# Control_Moway.net
KiCad netlist of a schematic drawn in Altium Designer
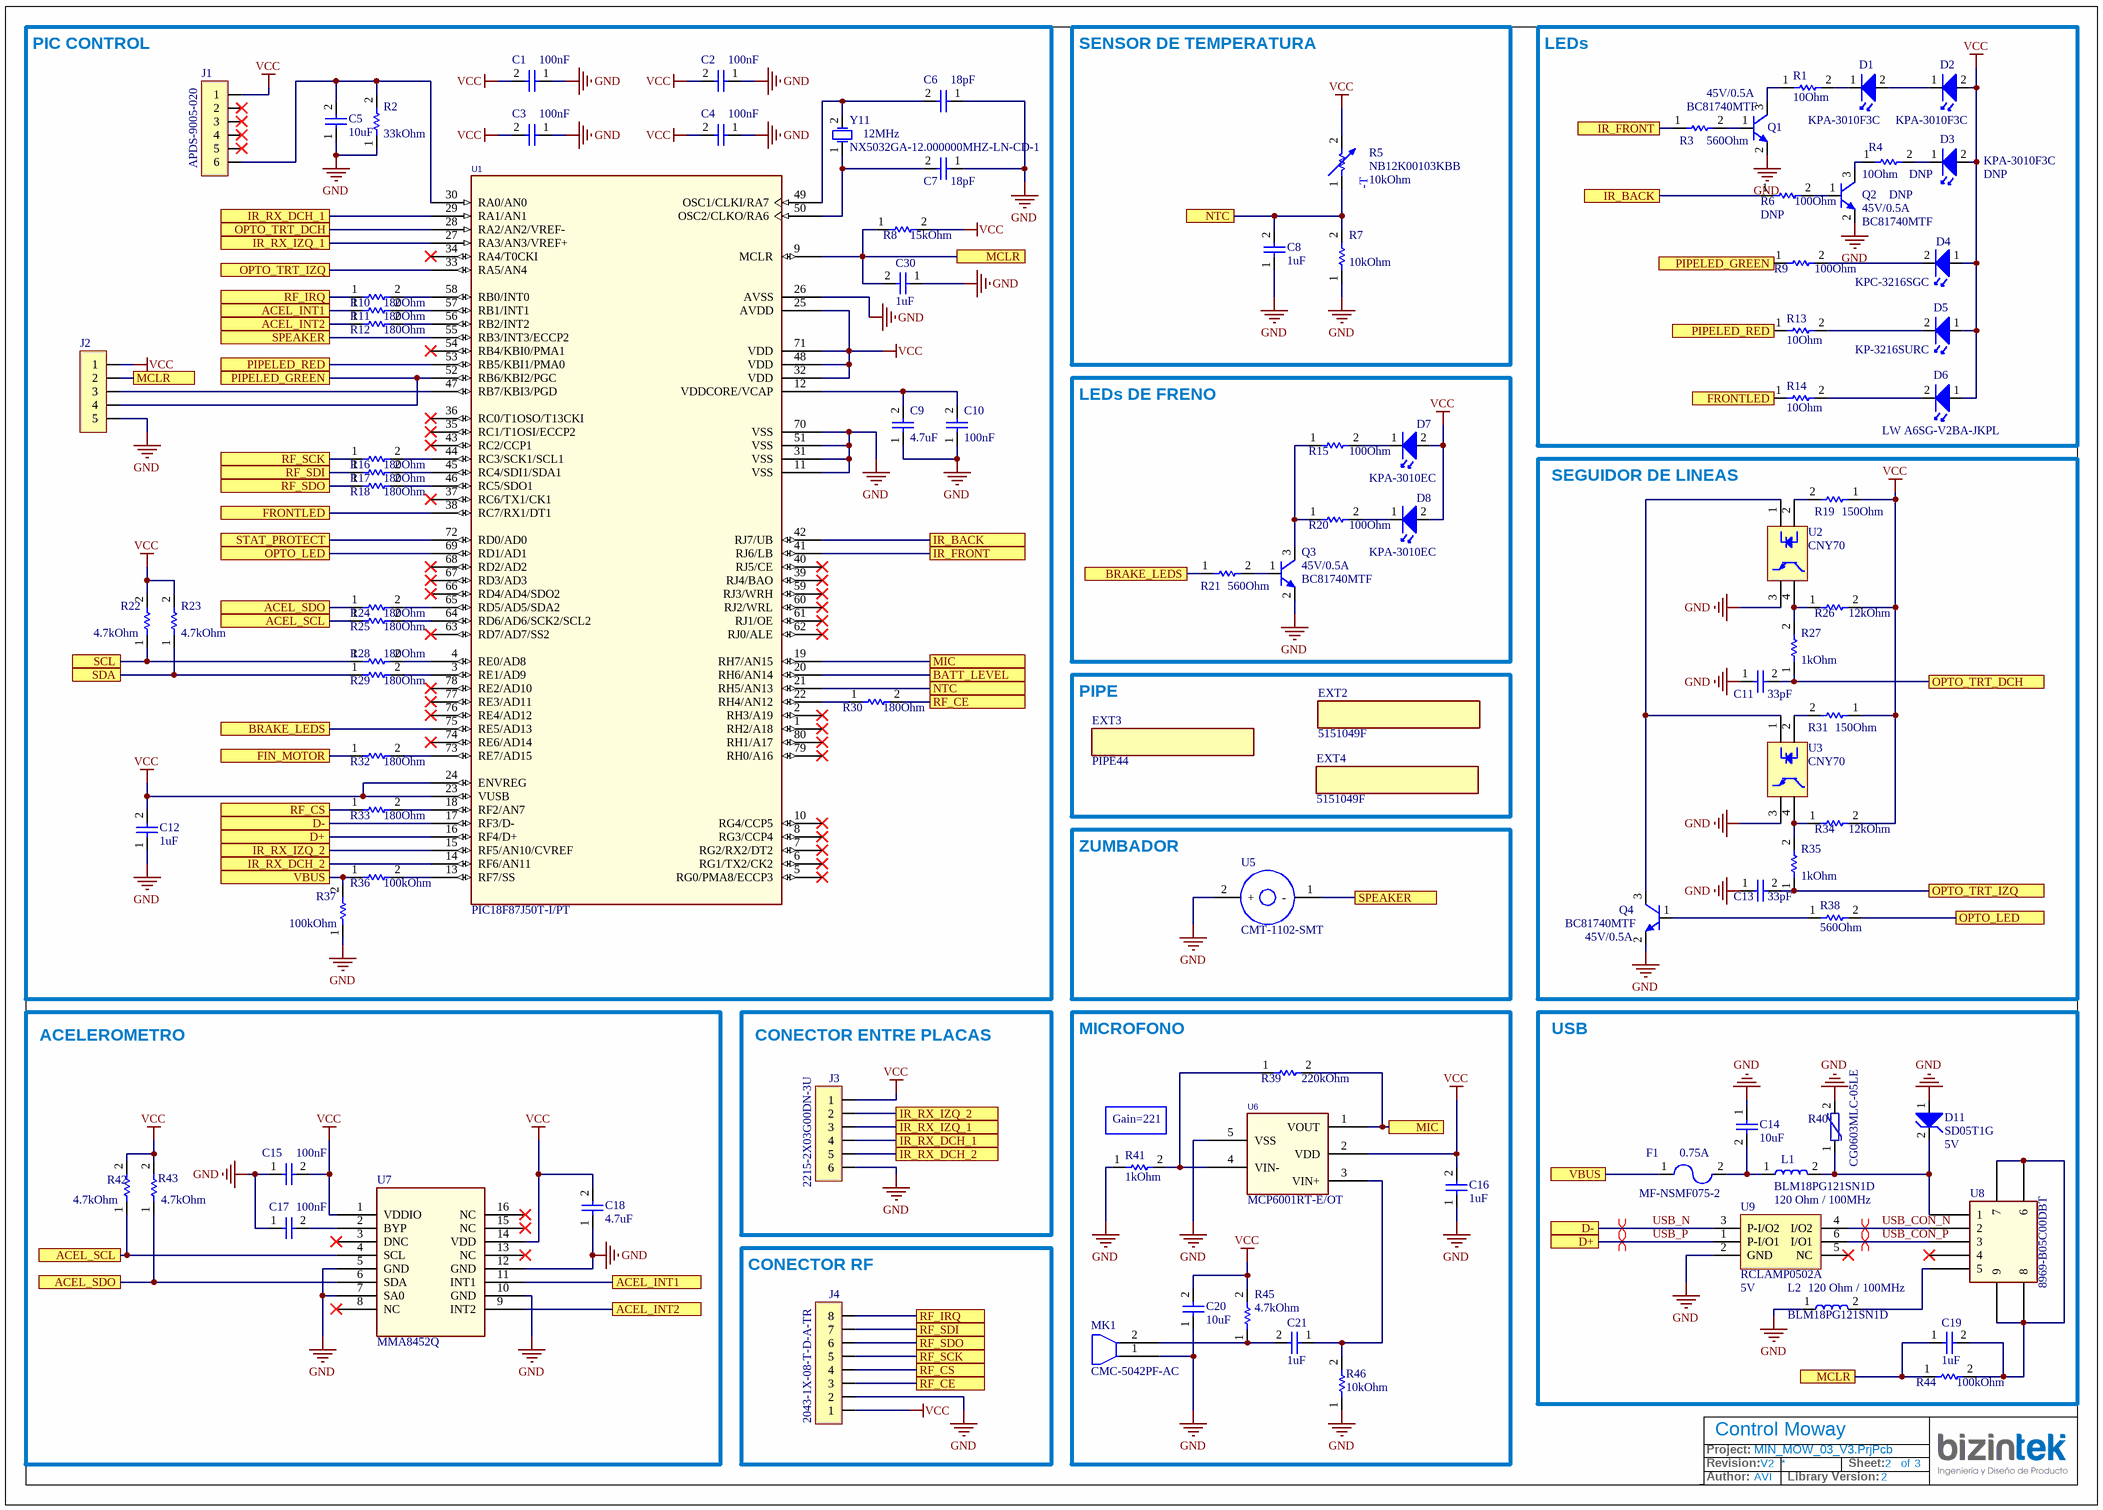
[diagram p0: Control_Moway.SchDoc]

(export (version "E")
  (design (tool "Eeschema 10.0.6"))
  (components
    (comp (ref "C1")
      (value "100nF")
      (footprint "C0402")
      (description "CAPACITOR SMD 0402, 100nF, 10V, X7R")
      (fields (field (name "PART NUMBER") "C100NV10X7R0402") (field (name "VOLTAGE") "10"))
      (libsource (lib "BZI_ALTIUMLIB") (part "CAPACITOR"))
    )
    (comp (ref "C2")
      (value "100nF")
      (footprint "C0402")
      (description "CAPACITOR SMD 0402, 100nF, 10V, X7R")
      (fields (field (name "PART NUMBER") "C100NV10X7R0402") (field (name "VOLTAGE") "10"))
      (libsource (lib "BZI_ALTIUMLIB") (part "CAPACITOR"))
    )
    (comp (ref "C3")
      (value "100nF")
      (footprint "C0402")
      (description "CAPACITOR SMD 0402, 100nF, 10V, X7R")
      (fields (field (name "PART NUMBER") "C100NV10X7R0402") (field (name "VOLTAGE") "10"))
      (libsource (lib "BZI_ALTIUMLIB") (part "CAPACITOR"))
    )
    (comp (ref "C4")
      (value "100nF")
      (footprint "C0402")
      (description "CAPACITOR SMD 0402, 100nF, 10V, X7R")
      (fields (field (name "PART NUMBER") "C100NV10X7R0402") (field (name "VOLTAGE") "10"))
      (libsource (lib "BZI_ALTIUMLIB") (part "CAPACITOR"))
    )
    (comp (ref "C5")
      (value "10uF")
      (footprint "C0603")
      (description "CAPACITOR SMD 0603, 10uF, 10V, X5R")
      (fields (field (name "PART NUMBER") "C10UV10X5R0603") (field (name "VOLTAGE") "10"))
      (libsource (lib "BZI_ALTIUMLIB") (part "CAPACITOR"))
    )
    (comp (ref "C6")
      (value "18pF")
      (footprint "C0402")
      (description "CAPACITOR SMD 0402, 18pF, 10V, C0G")
      (fields (field (name "PART NUMBER") "C18PV10C0G0402"))
      (libsource (lib "BZI_ALTIUMLIB") (part "CAPACITOR"))
    )
    (comp (ref "C7")
      (value "18pF")
      (footprint "C0402")
      (description "CAPACITOR SMD 0402, 18pF, 10V, C0G")
      (fields (field (name "PART NUMBER") "C18PV10C0G0402"))
      (libsource (lib "BZI_ALTIUMLIB") (part "CAPACITOR"))
    )
    (comp (ref "C8")
      (value "1uF")
      (footprint "C0402")
      (description "CAPACITOR SMD 0402, 1uF, 10V, X5R")
      (fields (field (name "PART NUMBER") "C1UV10X5R0402"))
      (libsource (lib "BZI_ALTIUMLIB") (part "CAPACITOR"))
    )
    (comp (ref "C9")
      (value "4.7uF")
      (footprint "C0402")
      (description "CAPACITOR SMD 0402, 4.7uF, 10V, X5R")
      (fields (field (name "PART NUMBER") "C4U7V10X5R0402") (field (name "VOLTAGE") "10"))
      (libsource (lib "BZI_ALTIUMLIB") (part "CAPACITOR"))
    )
    (comp (ref "C10")
      (value "100nF")
      (footprint "C0402")
      (description "CAPACITOR SMD 0402, 100nF, 10V, X7R")
      (fields (field (name "PART NUMBER") "C100NV10X7R0402") (field (name "VOLTAGE") "10"))
      (libsource (lib "BZI_ALTIUMLIB") (part "CAPACITOR"))
    )
    (comp (ref "C11")
      (value "33pF")
      (footprint "C0603")
      (description "CAPACITOR SMD 0603, 33pF, 10V, C0G")
      (fields (field (name "PART NUMBER") "C33PV10C0G0603"))
      (libsource (lib "BZI_ALTIUMLIB") (part "CAPACITOR"))
    )
    (comp (ref "C12")
      (value "1uF")
      (footprint "C0402")
      (description "CAPACITOR SMD 0402, 1uF, 10V, X5R")
      (fields (field (name "PART NUMBER") "C1UV10X5R0402"))
      (libsource (lib "BZI_ALTIUMLIB") (part "CAPACITOR"))
    )
    (comp (ref "C13")
      (value "33pF")
      (footprint "C0603")
      (description "CAPACITOR SMD 0603, 33pF, 10V, C0G")
      (fields (field (name "PART NUMBER") "C33PV10C0G0603"))
      (libsource (lib "BZI_ALTIUMLIB") (part "CAPACITOR"))
    )
    (comp (ref "C14")
      (value "10uF")
      (footprint "C0603")
      (description "CAPACITOR SMD 0603, 10uF, 10V, X5R")
      (fields (field (name "PART NUMBER") "C10UV10X5R0603") (field (name "VOLTAGE") "10"))
      (libsource (lib "BZI_ALTIUMLIB") (part "CAPACITOR"))
    )
    (comp (ref "C15")
      (value "100nF")
      (footprint "C0402")
      (description "CAPACITOR SMD 0402, 100nF, 10V, X7R")
      (fields (field (name "PART NUMBER") "C100NV10X7R0402") (field (name "VOLTAGE") "10"))
      (libsource (lib "BZI_ALTIUMLIB") (part "CAPACITOR"))
    )
    (comp (ref "C16")
      (value "1uF")
      (footprint "C0402")
      (description "CAPACITOR SMD 0402, 1uF, 10V, X5R")
      (fields (field (name "PART NUMBER") "C1UV10X5R0402"))
      (libsource (lib "BZI_ALTIUMLIB") (part "CAPACITOR"))
    )
    (comp (ref "C17")
      (value "100nF")
      (footprint "C0402")
      (description "CAPACITOR SMD 0402, 100nF, 10V, X7R")
      (fields (field (name "PART NUMBER") "C100NV10X7R0402") (field (name "VOLTAGE") "10"))
      (libsource (lib "BZI_ALTIUMLIB") (part "CAPACITOR"))
    )
    (comp (ref "C18")
      (value "4.7uF")
      (footprint "C0402")
      (description "CAPACITOR SMD 0402, 4.7uF, 10V, X5R")
      (fields (field (name "PART NUMBER") "C4U7V10X5R0402") (field (name "VOLTAGE") "10"))
      (libsource (lib "BZI_ALTIUMLIB") (part "CAPACITOR"))
    )
    (comp (ref "C19")
      (value "1uF")
      (footprint "C0402")
      (description "CAPACITOR SMD 0402, 1uF, 10V, X5R")
      (fields (field (name "PART NUMBER") "C1UV10X5R0402"))
      (libsource (lib "BZI_ALTIUMLIB") (part "CAPACITOR"))
    )
    (comp (ref "C20")
      (value "10uF")
      (footprint "C0603")
      (description "CAPACITOR SMD 0603, 10uF, 10V, X5R")
      (fields (field (name "PART NUMBER") "C10UV10X5R0603") (field (name "VOLTAGE") "10"))
      (libsource (lib "BZI_ALTIUMLIB") (part "CAPACITOR"))
    )
    (comp (ref "C21")
      (value "1uF")
      (footprint "C0402")
      (description "CAPACITOR SMD 0402, 1uF, 10V, X5R")
      (fields (field (name "PART NUMBER") "C1UV10X5R0402"))
      (libsource (lib "BZI_ALTIUMLIB") (part "CAPACITOR"))
    )
    (comp (ref "C30")
      (value "1uF")
      (footprint "C0402")
      (description "CAPACITOR SMD 0402, 1uF, 10V, X5R")
      (fields (field (name "PART NUMBER") "C1UV10X5R0402"))
      (libsource (lib "BZI_ALTIUMLIB") (part "CAPACITOR"))
    )
    (comp (ref "D1")
      (value "KPA3010F3C")
      (footprint "KPA3010")
      (description "IR-LED, SMD, 3mm x 2mm x 1 mm, 1,2V, 20mA, 940nm")
      (fields
        (field (name "MANUFACTURER PART NUMBER") "KPA-3010F3C")
        (field (name "MANUFACTURER") "KINGBRIGHT")
      )
      (libsource (lib "BZI_ALTIUMLIB") (part "DIODE_LED_1K2A"))
    )
    (comp (ref "D2")
      (value "KPA3010F3C")
      (footprint "KPA3010")
      (description "IR-LED, SMD, 3mm x 2mm x 1 mm, 1,2V, 20mA, 940nm")
      (fields
        (field (name "MANUFACTURER PART NUMBER") "KPA-3010F3C")
        (field (name "MANUFACTURER") "KINGBRIGHT")
      )
      (libsource (lib "BZI_ALTIUMLIB") (part "DIODE_LED_1K2A"))
    )
    (comp (ref "D3")
      (value "DNP")
      (footprint "KPA3010F3C_MOWAY")
      (description "IR-LED, SMD, 3mm x 2mm x 1 mm, 1,2V, 20mA, 940nm")
      (fields
        (field (name "PART NUMBER") "KPA3010F3C_MOWAY")
        (field (name "MANUFACTURER") "KINGBRIGHT")
        (field (name "MANUFACTURER PART NUMBER") "KPA-3010F3C")
      )
      (libsource (lib "BZI_ALTIUMLIB") (part "DIODE_LED_1K2A"))
    )
    (comp (ref "D4")
      (value "KPC3216SGC")
      (footprint "LED1206G")
      (description "LED, Low Power, Green, SMD, 1.6mm x 2mm, 20mA, 2.2V, 568nm")
      (fields
        (field (name "MANUFACTURER PART NUMBER") "KPC-3216SGC")
        (field (name "MANUFACTURER") "KINGBRIGHT")
      )
      (libsource (lib "BZI_ALTIUMLIB") (part "DIODE_LED"))
    )
    (comp (ref "D5")
      (value "KP3216SURC")
      (footprint "LED1206")
      (description "LED, Low Power, Red, SMD, 20 mA, 1.9 V, 628 nm")
      (fields
        (field (name "MANUFACTURER PART NUMBER") "KP-3216SURC")
        (field (name "MANUFACTURER") "KINGBRIGHT")
      )
      (libsource (lib "BZI_ALTIUMLIB") (part "DIODE_LED"))
    )
    (comp (ref "D6")
      (value "LWA6SGV2BAJKPL")
      (footprint "LWA6SG")
      (description "LED Osram Opto, White, 4.5 lm, 5600K, 3.2 V, 120°, SIDELED serie")
      (fields
        (field (name "MANUFACTURER PART NUMBER") "LW A6SG-V2BA-JKPL")
        (field (name "MANUFACTURER") "OSRAM")
      )
      (libsource (lib "BZI_ALTIUMLIB") (part "DIODE_LED"))
    )
    (comp (ref "D7")
      (value "KPA3010EC")
      (footprint "KPA3010")
      (description "LED, Right Angle, Red, SMD, 20mA, 2V, 617nm")
      (fields
        (field (name "MANUFACTURER PART NUMBER") "KPA-3010EC")
        (field (name "MANUFACTURER") "KINGBRIGHT")
      )
      (libsource (lib "BZI_ALTIUMLIB") (part "DIODE_LED_1K2A"))
    )
    (comp (ref "D8")
      (value "KPA3010EC")
      (footprint "KPA3010")
      (description "LED, Right Angle, Red, SMD, 20mA, 2V, 617nm")
      (fields
        (field (name "MANUFACTURER PART NUMBER") "KPA-3010EC")
        (field (name "MANUFACTURER") "KINGBRIGHT")
      )
      (libsource (lib "BZI_ALTIUMLIB") (part "DIODE_LED_1K2A"))
    )
    (comp (ref "D11")
      (value "5V")
      (footprint "SOD323_ONSEMI")
      (description "TVS Diode, SD05T1 Series, Unidirectional, 5 V, 14.5 V, SOD-323, 2 Pins")
      (fields
        (field (name "PART NUMBER") "SD05T1G")
        (field (name "MANUFACTURER PART NUMBER") "SD05T1G")
        (field (name "MANUFACTURER") "ON SEMICONDUCTOR")
      )
      (libsource (lib "BZI_ALTIUMLIB") (part "DIODE_ZENER"))
    )
    (comp (ref "EXT2")
      (value "5151049F")
      (footprint "5151049F")
      (description "LIGHT PIPE")
      (fields (field (name "MANUFACTURER PART NUMBER") "5151049F") (field (name "MANUFACTURER") "DIALIGHT"))
      (libsource (lib "BZI_ALTIUMLIB") (part "EXTERNAL_GEN"))
    )
    (comp (ref "EXT3")
      (value "PIPE44")
      (footprint "PIPE44_MR")
      (description "Light Pipe")
      (fields (field (name "MANUFACTURER PART NUMBER") "PIPE44") (field (name "MANUFACTURER") "MINIROBOTS"))
      (libsource (lib "BZI_ALTIUMLIB") (part "EXTERNAL_GEN"))
    )
    (comp (ref "EXT4")
      (value "5151049F")
      (footprint "5151049F")
      (description "LIGHT PIPE")
      (fields (field (name "MANUFACTURER PART NUMBER") "5151049F") (field (name "MANUFACTURER") "DIALIGHT"))
      (libsource (lib "BZI_ALTIUMLIB") (part "EXTERNAL_GEN"))
    )
    (comp (ref "F1")
      (value "0.75A")
      (footprint "F1206")
      (description "PPTC Resettable Fuse, SMD, MF-NSMF Series, 750 mA, 1.5 A, 6 V, -40 °C")
      (fields
        (field (name "PART NUMBER") "MFNSMF0752")
        (field (name "MANUFACTURER PART NUMBER") "MF-NSMF075-2")
        (field (name "MANUFACTURER") "BOURNS")
      )
      (libsource (lib "BZI_ALTIUMLIB") (part "FUSE"))
    )
    (comp (ref "J1")
      (value "APDS9005020")
      (footprint "APDS9005020")
      (description "Ambient Light Photosensor, APDS-9005, Miniature, SMD, chipLED, Analogue, 1.8 V to 5.5 V")
      (fields (field (name "MANUFACTURER PART NUMBER") "APDS-9005-020") (field (name "MANUFACTURER") "AVAGO"))
      (libsource (lib "BZI_ALTIUMLIB") (part "HEADER_6PIN"))
    )
    (comp (ref "J2")
      (value "PAD_5PIN_TH_2X1MM_1.5MM_PITCH")
      (footprint "PAD_5PIN_TH_2X1MM_1.5MM_PITCH")
      (libsource (lib "BZI_ALTIUMLIB") (part "HEADER_5PIN"))
    )
    (comp (ref "J3")
      (value "2215203G00DN3U")
      (footprint "22152X03_OUPIIN")
      (description "Board to Board connector, SMD, 6 pin, 1.27 pitch")
      (fields
        (field (name "MANUFACTURER PART NUMBER") "2215-2X03G00DN-3U")
        (field (name "MANUFACTURER") "OUPIIN")
      )
      (libsource (lib "BZI_ALTIUMLIB") (part "HEADER_6PIN"))
    )
    (comp (ref "J4")
      (value "20431X08TDATR")
      (footprint "20431X08TDATR_OUPIIN")
      (description "Expansion Connector, 8 pin, SMD Female")
      (fields
        (field (name "MANUFACTURER PART NUMBER") "2043-1X-08-T-D-A-TR")
        (field (name "MANUFACTURER") "OUPIIN")
      )
      (libsource (lib "BZI_ALTIUMLIB") (part "HEADER_8PIN"))
    )
    (comp (ref "L1")
      (value "120 Ohm / 100MHz")
      (footprint "L0603")
      (description "INDUCTOR SMD 120 Ohm / 100MHz, 2A, 0603")
      (fields
        (field (name "PART NUMBER") "BLM18PG121SN1D")
        (field (name "MANUFACTURER PART NUMBER") "BLM18PG121SN1D")
        (field (name "MANUFACTURER") "MURATA")
      )
      (libsource (lib "BZI_ALTIUMLIB") (part "INDUCTOR"))
    )
    (comp (ref "L2")
      (value "120 Ohm / 100MHz")
      (footprint "L0603")
      (description "INDUCTOR SMD 120 Ohm / 100MHz, 2A, 0603")
      (fields
        (field (name "PART NUMBER") "BLM18PG121SN1D")
        (field (name "MANUFACTURER PART NUMBER") "BLM18PG121SN1D")
        (field (name "MANUFACTURER") "MURATA")
      )
      (libsource (lib "BZI_ALTIUMLIB") (part "INDUCTOR"))
    )
    (comp (ref "MK1")
      (value "CMC5042PFAC")
      (footprint "CMC5042PFAC")
      (description "Electret Condenser Microphone")
      (fields (field (name "MANUFACTURER PART NUMBER") "CMC-5042PF-AC") (field (name "MANUFACTURER") "CUI"))
      (libsource (lib "BZI_ALTIUMLIB") (part "CMC5042PFAC"))
    )
    (comp (ref "Q1")
      (value "45V/0.5A")
      (footprint "SOT23_FAIRCHILD")
      (description "Bipolar (BJT) Single Transistor, NPN, 45 V, 170 MHz, 300 mW, 500 mA, 250 hFE")
      (fields
        (field (name "PART NUMBER") "BC81740MTF")
        (field (name "MANUFACTURER PART NUMBER") "BC81740MTF")
        (field (name "MANUFACTURER") "FAIRCHILD")
      )
      (libsource (lib "BZI_ALTIUMLIB") (part "BJT_NPN"))
    )
    (comp (ref "Q2")
      (value "DNP")
      (footprint "SOT23_FAIRCHILD")
      (description "Bipolar (BJT) Single Transistor, NPN, 45 V, 170 MHz, 300 mW, 500 mA, 250 hFE")
      (fields
        (field (name "PART NUMBER") "BC81740MTF")
        (field (name "MANUFACTURER PART NUMBER") "BC81740MTF")
        (field (name "MANUFACTURER") "FAIRCHILD")
        (field (name "ALTIUM_VALUE") "45V/0.5A")
      )
      (libsource (lib "BZI_ALTIUMLIB") (part "BJT_NPN"))
    )
    (comp (ref "Q3")
      (value "45V/0.5A")
      (footprint "SOT23_FAIRCHILD")
      (description "Bipolar (BJT) Single Transistor, NPN, 45 V, 170 MHz, 300 mW, 500 mA, 250 hFE")
      (fields
        (field (name "PART NUMBER") "BC81740MTF")
        (field (name "MANUFACTURER PART NUMBER") "BC81740MTF")
        (field (name "MANUFACTURER") "FAIRCHILD")
      )
      (libsource (lib "BZI_ALTIUMLIB") (part "BJT_NPN"))
    )
    (comp (ref "Q4")
      (value "45V/0.5A")
      (footprint "SOT23_FAIRCHILD")
      (description "Bipolar (BJT) Single Transistor, NPN, 45 V, 170 MHz, 300 mW, 500 mA, 250 hFE")
      (fields
        (field (name "PART NUMBER") "BC81740MTF")
        (field (name "MANUFACTURER PART NUMBER") "BC81740MTF")
        (field (name "MANUFACTURER") "FAIRCHILD")
      )
      (libsource (lib "BZI_ALTIUMLIB") (part "BJT_NPN"))
    )
    (comp (ref "R1")
      (value "10Ohm")
      (footprint "R0402")
      (description "RESISTOR SMD 0402, 10Ohm, 1%")
      (fields (field (name "PART NUMBER") "R10T10402") (field (name "TOLERANCE") "1"))
      (libsource (lib "BZI_ALTIUMLIB") (part "RESISTOR"))
    )
    (comp (ref "R2")
      (value "33kOhm")
      (footprint "R0402")
      (description "RESISTOR SMD 0402, 33kOhm, 1%")
      (fields (field (name "PART NUMBER") "R33KT10402") (field (name "TOLERANCE") "1"))
      (libsource (lib "BZI_ALTIUMLIB") (part "RESISTOR"))
    )
    (comp (ref "R3")
      (value "560Ohm")
      (footprint "R0402")
      (description "RESISTOR SMD 0402, 560Ohm, 1%")
      (fields (field (name "PART NUMBER") "R560T10402") (field (name "TOLERANCE") "1"))
      (libsource (lib "BZI_ALTIUMLIB") (part "RESISTOR"))
    )
    (comp (ref "R4")
      (value "DNP")
      (footprint "R0402")
      (description "RESISTOR SMD 0402, 10Ohm, 1%")
      (fields
        (field (name "PART NUMBER") "R10T10402")
        (field (name "ALTIUM_VALUE") "10Ohm")
        (field (name "TOLERANCE") "1")
      )
      (libsource (lib "BZI_ALTIUMLIB") (part "RESISTOR"))
    )
    (comp (ref "R5")
      (value "10kOhm")
      (footprint "R0805")
      (description "Thermistor, NTC, 10 kohm, NB12 Series, 3630 K, SMD, 0805")
      (fields
        (field (name "PART NUMBER") "NB12K00103KBB")
        (field (name "MANUFACTURER PART NUMBER") "NB12K00103KBB")
        (field (name "MANUFACTURER") "AVX")
      )
      (libsource (lib "BZI_ALTIUMLIB") (part "NTC"))
    )
    (comp (ref "R6")
      (value "DNP")
      (footprint "R0402")
      (description "RESISTOR SMD 0402, 100Ohm, 1%")
      (fields
        (field (name "PART NUMBER") "R100T10402")
        (field (name "ALTIUM_VALUE") "100Ohm")
        (field (name "TOLERANCE") "1")
      )
      (libsource (lib "BZI_ALTIUMLIB") (part "RESISTOR"))
    )
    (comp (ref "R7")
      (value "10kOhm")
      (footprint "R0402")
      (description "RESISTOR SMD 0402, 10kOhm, 1%")
      (fields (field (name "PART NUMBER") "R10KT10402") (field (name "TOLERANCE") "1"))
      (libsource (lib "BZI_ALTIUMLIB") (part "RESISTOR"))
    )
    (comp (ref "R8")
      (value "15kOhm")
      (footprint "R0402")
      (description "RESISTOR SMD 0402, 15kOhm, 1%")
      (fields (field (name "PART NUMBER") "R15KT10402") (field (name "TOLERANCE") "1"))
      (libsource (lib "BZI_ALTIUMLIB") (part "RESISTOR"))
    )
    (comp (ref "R9")
      (value "100Ohm")
      (footprint "R0402")
      (description "RESISTOR SMD 0402, 100Ohm, 1%")
      (fields (field (name "PART NUMBER") "R100T10402") (field (name "TOLERANCE") "1"))
      (libsource (lib "BZI_ALTIUMLIB") (part "RESISTOR"))
    )
    (comp (ref "R10")
      (value "180Ohm")
      (footprint "R0402")
      (description "RESISTOR SMD 0402, 180Ohm, 1%")
      (fields (field (name "PART NUMBER") "R180T10402") (field (name "TOLERANCE") "1"))
      (libsource (lib "BZI_ALTIUMLIB") (part "RESISTOR"))
    )
    (comp (ref "R11")
      (value "180Ohm")
      (footprint "R0402")
      (description "RESISTOR SMD 0402, 180Ohm, 1%")
      (fields (field (name "PART NUMBER") "R180T10402") (field (name "TOLERANCE") "1"))
      (libsource (lib "BZI_ALTIUMLIB") (part "RESISTOR"))
    )
    (comp (ref "R12")
      (value "180Ohm")
      (footprint "R0402")
      (description "RESISTOR SMD 0402, 180Ohm, 1%")
      (fields (field (name "PART NUMBER") "R180T10402") (field (name "TOLERANCE") "1"))
      (libsource (lib "BZI_ALTIUMLIB") (part "RESISTOR"))
    )
    (comp (ref "R13")
      (value "10Ohm")
      (footprint "R0402")
      (description "RESISTOR SMD 0402, 10Ohm, 1%")
      (fields (field (name "PART NUMBER") "R10T10402") (field (name "TOLERANCE") "1"))
      (libsource (lib "BZI_ALTIUMLIB") (part "RESISTOR"))
    )
    (comp (ref "R14")
      (value "10Ohm")
      (footprint "R0402")
      (description "RESISTOR SMD 0402, 10Ohm, 1%")
      (fields (field (name "PART NUMBER") "R10T10402") (field (name "TOLERANCE") "1"))
      (libsource (lib "BZI_ALTIUMLIB") (part "RESISTOR"))
    )
    (comp (ref "R15")
      (value "100Ohm")
      (footprint "R0402")
      (description "RESISTOR SMD 0402, 100Ohm, 1%")
      (fields (field (name "PART NUMBER") "R100T10402") (field (name "TOLERANCE") "1"))
      (libsource (lib "BZI_ALTIUMLIB") (part "RESISTOR"))
    )
    (comp (ref "R16")
      (value "180Ohm")
      (footprint "R0402")
      (description "RESISTOR SMD 0402, 180Ohm, 1%")
      (fields (field (name "PART NUMBER") "R180T10402") (field (name "TOLERANCE") "1"))
      (libsource (lib "BZI_ALTIUMLIB") (part "RESISTOR"))
    )
    (comp (ref "R17")
      (value "180Ohm")
      (footprint "R0402")
      (description "RESISTOR SMD 0402, 180Ohm, 1%")
      (fields (field (name "PART NUMBER") "R180T10402") (field (name "TOLERANCE") "1"))
      (libsource (lib "BZI_ALTIUMLIB") (part "RESISTOR"))
    )
    (comp (ref "R18")
      (value "180Ohm")
      (footprint "R0402")
      (description "RESISTOR SMD 0402, 180Ohm, 1%")
      (fields (field (name "PART NUMBER") "R180T10402") (field (name "TOLERANCE") "1"))
      (libsource (lib "BZI_ALTIUMLIB") (part "RESISTOR"))
    )
    (comp (ref "R19")
      (value "150Ohm")
      (footprint "R0402")
      (description "RESISTOR SMD 0402, 150Ohm, 1%")
      (fields (field (name "PART NUMBER") "R150T10402") (field (name "TOLERANCE") "1"))
      (libsource (lib "BZI_ALTIUMLIB") (part "RESISTOR"))
    )
    (comp (ref "R20")
      (value "100Ohm")
      (footprint "R0402")
      (description "RESISTOR SMD 0402, 100Ohm, 1%")
      (fields (field (name "PART NUMBER") "R100T10402") (field (name "TOLERANCE") "1"))
      (libsource (lib "BZI_ALTIUMLIB") (part "RESISTOR"))
    )
    (comp (ref "R21")
      (value "560Ohm")
      (footprint "R0402")
      (description "RESISTOR SMD 0402, 560Ohm, 1%")
      (fields (field (name "PART NUMBER") "R560T10402") (field (name "TOLERANCE") "1"))
      (libsource (lib "BZI_ALTIUMLIB") (part "RESISTOR"))
    )
    (comp (ref "R22")
      (value "4.7kOhm")
      (footprint "R0402")
      (description "RESISTOR SMD 0402, 4.7kOhm, 1%")
      (fields (field (name "PART NUMBER") "R4K7T10402") (field (name "TOLERANCE") "1"))
      (libsource (lib "BZI_ALTIUMLIB") (part "RESISTOR"))
    )
    (comp (ref "R23")
      (value "4.7kOhm")
      (footprint "R0402")
      (description "RESISTOR SMD 0402, 4.7kOhm, 1%")
      (fields (field (name "PART NUMBER") "R4K7T10402") (field (name "TOLERANCE") "1"))
      (libsource (lib "BZI_ALTIUMLIB") (part "RESISTOR"))
    )
    (comp (ref "R24")
      (value "180Ohm")
      (footprint "R0402")
      (description "RESISTOR SMD 0402, 180Ohm, 1%")
      (fields (field (name "PART NUMBER") "R180T10402") (field (name "TOLERANCE") "1"))
      (libsource (lib "BZI_ALTIUMLIB") (part "RESISTOR"))
    )
    (comp (ref "R25")
      (value "180Ohm")
      (footprint "R0402")
      (description "RESISTOR SMD 0402, 180Ohm, 1%")
      (fields (field (name "PART NUMBER") "R180T10402") (field (name "TOLERANCE") "1"))
      (libsource (lib "BZI_ALTIUMLIB") (part "RESISTOR"))
    )
    (comp (ref "R26")
      (value "12kOhm")
      (footprint "R0402")
      (description "RESISTOR SMD 0402, 12kOhm, 1%")
      (fields (field (name "PART NUMBER") "R12KT10402") (field (name "TOLERANCE") "1"))
      (libsource (lib "BZI_ALTIUMLIB") (part "RESISTOR"))
    )
    (comp (ref "R27")
      (value "1kOhm")
      (footprint "R0402")
      (description "RESISTOR SMD 0402, 1kOhm, 1%")
      (fields (field (name "PART NUMBER") "R1KT10402") (field (name "TOLERANCE") "1"))
      (libsource (lib "BZI_ALTIUMLIB") (part "RESISTOR"))
    )
    (comp (ref "R28")
      (value "180Ohm")
      (footprint "R0402")
      (description "RESISTOR SMD 0402, 180Ohm, 1%")
      (fields (field (name "PART NUMBER") "R180T10402") (field (name "TOLERANCE") "1"))
      (libsource (lib "BZI_ALTIUMLIB") (part "RESISTOR"))
    )
    (comp (ref "R29")
      (value "180Ohm")
      (footprint "R0402")
      (description "RESISTOR SMD 0402, 180Ohm, 1%")
      (fields (field (name "PART NUMBER") "R180T10402") (field (name "TOLERANCE") "1"))
      (libsource (lib "BZI_ALTIUMLIB") (part "RESISTOR"))
    )
    (comp (ref "R30")
      (value "180Ohm")
      (footprint "R0402")
      (description "RESISTOR SMD 0402, 180Ohm, 1%")
      (fields (field (name "PART NUMBER") "R180T10402") (field (name "TOLERANCE") "1"))
      (libsource (lib "BZI_ALTIUMLIB") (part "RESISTOR"))
    )
    (comp (ref "R31")
      (value "150Ohm")
      (footprint "R0402")
      (description "RESISTOR SMD 0402, 150Ohm, 1%")
      (fields (field (name "PART NUMBER") "R150T10402") (field (name "TOLERANCE") "1"))
      (libsource (lib "BZI_ALTIUMLIB") (part "RESISTOR"))
    )
    (comp (ref "R32")
      (value "180Ohm")
      (footprint "R0402")
      (description "RESISTOR SMD 0402, 180Ohm, 1%")
      (fields (field (name "PART NUMBER") "R180T10402") (field (name "TOLERANCE") "1"))
      (libsource (lib "BZI_ALTIUMLIB") (part "RESISTOR"))
    )
    (comp (ref "R33")
      (value "180Ohm")
      (footprint "R0402")
      (description "RESISTOR SMD 0402, 180Ohm, 1%")
      (fields (field (name "PART NUMBER") "R180T10402") (field (name "TOLERANCE") "1"))
      (libsource (lib "BZI_ALTIUMLIB") (part "RESISTOR"))
    )
    (comp (ref "R34")
      (value "12kOhm")
      (footprint "R0402")
      (description "RESISTOR SMD 0402, 12kOhm, 1%")
      (fields (field (name "PART NUMBER") "R12KT10402") (field (name "TOLERANCE") "1"))
      (libsource (lib "BZI_ALTIUMLIB") (part "RESISTOR"))
    )
    (comp (ref "R35")
      (value "1kOhm")
      (footprint "R0402")
      (description "RESISTOR SMD 0402, 1kOhm, 1%")
      (fields (field (name "PART NUMBER") "R1KT10402") (field (name "TOLERANCE") "1"))
      (libsource (lib "BZI_ALTIUMLIB") (part "RESISTOR"))
    )
    (comp (ref "R36")
      (value "100kOhm")
      (footprint "R0402")
      (description "RESISTOR SMD 0402, 100kOhm, 1%")
      (fields (field (name "PART NUMBER") "R100KT10402") (field (name "TOLERANCE") "1"))
      (libsource (lib "BZI_ALTIUMLIB") (part "RESISTOR"))
    )
    (comp (ref "R37")
      (value "100kOhm")
      (footprint "R0402")
      (description "RESISTOR SMD 0402, 100kOhm, 1%")
      (fields (field (name "PART NUMBER") "R100KT10402") (field (name "TOLERANCE") "1"))
      (libsource (lib "BZI_ALTIUMLIB") (part "RESISTOR"))
    )
    (comp (ref "R38")
      (value "560Ohm")
      (footprint "R0402")
      (description "RESISTOR SMD 0402, 560Ohm, 1%")
      (fields (field (name "PART NUMBER") "R560T10402") (field (name "TOLERANCE") "1"))
      (libsource (lib "BZI_ALTIUMLIB") (part "RESISTOR"))
    )
    (comp (ref "R39")
      (value "220kOhm")
      (footprint "R0402")
      (description "RESISTOR SMD 0402, 220kOhm, 1%")
      (fields (field (name "PART NUMBER") "R220KT10402") (field (name "TOLERANCE") "1"))
      (libsource (lib "BZI_ALTIUMLIB") (part "RESISTOR"))
    )
    (comp (ref "R40")
      (value "CG0603MLC05LE")
      (footprint "V0603")
      (description "Varistor SMD")
      (fields
        (field (name "MANUFACTURER PART NUMBER") "CG0603MLC-05LE")
        (field (name "MANUFACTURER") "BOURNS")
      )
      (libsource (lib "BZI_ALTIUMLIB") (part "VARISTOR"))
    )
    (comp (ref "R41")
      (value "1kOhm")
      (footprint "R0402")
      (description "RESISTOR SMD 0402, 1kOhm, 1%")
      (fields (field (name "PART NUMBER") "R1KT10402") (field (name "TOLERANCE") "1"))
      (libsource (lib "BZI_ALTIUMLIB") (part "RESISTOR"))
    )
    (comp (ref "R42")
      (value "4.7kOhm")
      (footprint "R0402")
      (description "RESISTOR SMD 0402, 4.7kOhm, 1%")
      (fields (field (name "PART NUMBER") "R4K7T10402") (field (name "TOLERANCE") "1"))
      (libsource (lib "BZI_ALTIUMLIB") (part "RESISTOR"))
    )
    (comp (ref "R43")
      (value "4.7kOhm")
      (footprint "R0402")
      (description "RESISTOR SMD 0402, 4.7kOhm, 1%")
      (fields (field (name "PART NUMBER") "R4K7T10402") (field (name "TOLERANCE") "1"))
      (libsource (lib "BZI_ALTIUMLIB") (part "RESISTOR"))
    )
    (comp (ref "R44")
      (value "100kOhm")
      (footprint "R0402")
      (description "RESISTOR SMD 0402, 100kOhm, 1%")
      (fields (field (name "PART NUMBER") "R100KT10402") (field (name "TOLERANCE") "1"))
      (libsource (lib "BZI_ALTIUMLIB") (part "RESISTOR"))
    )
    (comp (ref "R45")
      (value "4.7kOhm")
      (footprint "R0402")
      (description "RESISTOR SMD 0402, 4.7kOhm, 1%")
      (fields (field (name "PART NUMBER") "R4K7T10402") (field (name "TOLERANCE") "1"))
      (libsource (lib "BZI_ALTIUMLIB") (part "RESISTOR"))
    )
    (comp (ref "R46")
      (value "10kOhm")
      (footprint "R0402")
      (description "RESISTOR SMD 0402, 10kOhm, 1%")
      (fields (field (name "PART NUMBER") "R10KT10402") (field (name "TOLERANCE") "1"))
      (libsource (lib "BZI_ALTIUMLIB") (part "RESISTOR"))
    )
    (comp (ref "U1")
      (value "PIC18F87J50TIPT")
      (footprint "TQFP80_MCP")
      (description "80-pin 1-Mbit FLASH USB MCU")
      (fields
        (field (name "MANUFACTURER PART NUMBER") "PIC18F87J50T-I/PT")
        (field (name "MANUFACTURER") "MICROCHIP")
      )
      (libsource (lib "BZI_ALTIUMLIB") (part "PIC18F87J50TIPT"))
    )
    (comp (ref "U2") (value "CNY70") (libsource (lib "CNY70") (part "CNY70")))
    (comp (ref "U3") (value "CNY70") (libsource (lib "CNY70") (part "CNY70")))
    (comp (ref "U5")
      (value "CMT1102SMT")
      (footprint "CMT1102SMT")
      (description "PIEZO BUZZER TRANSDUCER, 73dB a 5V  10cm")
      (fields (field (name "MANUFACTURER PART NUMBER") "CMT-1102-SMT") (field (name "MANUFACTURER") "CUI"))
      (libsource (lib "BZI_ALTIUMLIB") (part "BUZZER"))
    )
    (comp (ref "U6")
      (value "MCP6001RTEOT")
      (footprint "SOT23-5_MCP")
      (description "1MHz Low-Power Op Amp")
      (fields
        (field (name "MANUFACTURER PART NUMBER") "MCP6001RT-E/OT")
        (field (name "MANUFACTURER") "MICROCHIP")
      )
      (libsource (lib "BZI_ALTIUMLIB") (part "MCP6001RTEOT"))
    )
    (comp (ref "U7")
      (value "MMA8452Q")
      (footprint "QFN16-5x3_NXP")
      (description "MEMS Accelerometer, 3-Axis, Digital, X, Y, Z, ± 2g, ± 4g, ± 8g, 1.95 V, 3.6 V, QFN")
      (fields (field (name "MANUFACTURER PART NUMBER") "MMA8452Q") (field (name "MANUFACTURER") "NXP"))
      (libsource (lib "BZI_ALTIUMLIB") (part "MMA8452Q"))
    )
    (comp (ref "U8")
      (value "8969B05C00DBT")
      (footprint "8969B05C00DBT_OUPIIN")
      (description "USB Connector, Mini USB Type B, 5 Ways, SMD")
      (fields
        (field (name "MANUFACTURER PART NUMBER") "8969-B05C00DBT")
        (field (name "MANUFACTURER") "OUPIIN")
      )
      (libsource (lib "BZI_ALTIUMLIB") (part "8969B05C00DBT"))
    )
    (comp (ref "U9")
      (value "5V")
      (footprint "SOT666_SEMTECH")
      (description "TVS Diode, RailClamp Series, 5 V, 18 V, SOT-666, 6 Pins")
      (fields
        (field (name "PART NUMBER") "RCLAMP0502A")
        (field (name "MANUFACTURER PART NUMBER") "RCLAMP0502A")
        (field (name "MANUFACTURER") "SEMTECH")
      )
      (libsource (lib "BZI_ALTIUMLIB") (part "RCLAMP0502ATCT"))
    )
    (comp (ref "Y11")
      (value "12MHz")
      (footprint "NX5032GA_NDK")
      (description "Crystal, 12MHz, SMD, 5mm x 3.2mm, 8pF, 50ppm")
      (fields
        (field (name "PART NUMBER") "NX5032GA12000000MHZLNCD1")
        (field (name "MANUFACTURER PART NUMBER") "NX5032GA-12.000000MHZ-LN-CD-1")
        (field (name "MANUFACTURER") "NDK")
      )
      (libsource (lib "BZI_ALTIUMLIB") (part "XTAL_2PIN"))
    )
  )
  (nets
    (net (code "1") (name "/ACEL_INT1") (class "Default")
      (node (ref "R11") (pin "1") (pinfunction "1_1") (pintype "passive"))
      (node (ref "U7") (pin "11") (pinfunction "INT1_11") (pintype "passive"))
    )
    (net (code "2") (name "/ACEL_INT2") (class "Default")
      (node (ref "R12") (pin "1") (pinfunction "1_1") (pintype "passive"))
      (node (ref "U7") (pin "9") (pinfunction "INT2_9") (pintype "passive"))
    )
    (net (code "3") (name "/ACEL_SCL") (class "Default")
      (node (ref "R25") (pin "1") (pinfunction "1_1") (pintype "passive"))
      (node (ref "R42") (pin "1") (pinfunction "1_1") (pintype "passive"))
      (node (ref "U7") (pin "4") (pinfunction "SCL_4") (pintype "passive"))
    )
    (net (code "4") (name "/ACEL_SDO") (class "Default")
      (node (ref "R24") (pin "1") (pinfunction "1_1") (pintype "passive"))
      (node (ref "R43") (pin "1") (pinfunction "1_1") (pintype "passive"))
      (node (ref "U7") (pin "6") (pinfunction "SDA_6") (pintype "passive"))
    )
    (net (code "5") (name "/BATT_LEVEL") (class "Default")
      (node (ref "U1") (pin "20") (pinfunction "RH6/AN14_20") (pintype "bidirectional"))
    )
    (net (code "6") (name "/BRAKE_LEDS") (class "Default")
      (node (ref "R21") (pin "1") (pinfunction "1_1") (pintype "passive"))
      (node (ref "U1") (pin "75") (pinfunction "RE5/AD13_75") (pintype "bidirectional"))
    )
    (net (code "7") (name "/FIN_MOTOR") (class "Default")
      (node (ref "R32") (pin "1") (pinfunction "1_1") (pintype "passive"))
    )
    (net (code "8") (name "/FRONTLED") (class "Default")
      (node (ref "R14") (pin "1") (pinfunction "1_1") (pintype "passive"))
      (node (ref "U1") (pin "38") (pinfunction "RC7/RX1/DT1_38") (pintype "bidirectional"))
    )
    (net (code "9") (name "/IR_BACK") (class "Default")
      (node (ref "R6") (pin "1") (pinfunction "1_1") (pintype "passive"))
      (node (ref "U1") (pin "42") (pinfunction "RJ7/UB_42") (pintype "bidirectional"))
    )
    (net (code "10") (name "/IR_FRONT") (class "Default")
      (node (ref "R3") (pin "1") (pinfunction "1_1") (pintype "passive"))
      (node (ref "U1") (pin "41") (pinfunction "RJ6/LB_41") (pintype "bidirectional"))
    )
    (net (code "11") (name "/IR_RX_DCH_1") (class "Default")
      (node (ref "J3") (pin "4") (pinfunction "4_4") (pintype "passive"))
      (node (ref "U1") (pin "29") (pinfunction "RA1/AN1_29") (pintype "input"))
    )
    (net (code "12") (name "/IR_RX_DCH_2") (class "Default")
      (node (ref "J3") (pin "5") (pinfunction "5_5") (pintype "passive"))
      (node (ref "U1") (pin "14") (pinfunction "RF6/AN11_14") (pintype "bidirectional"))
    )
    (net (code "13") (name "/IR_RX_IZQ_1") (class "Default")
      (node (ref "J3") (pin "3") (pinfunction "3_3") (pintype "passive"))
      (node (ref "U1") (pin "27") (pinfunction "RA3/AN3/VREF+_27") (pintype "input"))
    )
    (net (code "14") (name "/IR_RX_IZQ_2") (class "Default")
      (node (ref "J3") (pin "2") (pinfunction "2_2") (pintype "passive"))
      (node (ref "U1") (pin "15") (pinfunction "RF5/AN10/CVREF_15") (pintype "bidirectional"))
    )
    (net (code "15") (name "/MCLR") (class "Default")
      (node (ref "C19") (pin "1") (pinfunction "1_1") (pintype "passive"))
      (node (ref "C30") (pin "2") (pinfunction "2_2") (pintype "passive"))
      (node (ref "J2") (pin "2") (pinfunction "2_2") (pintype "passive"))
      (node (ref "R44") (pin "1") (pinfunction "1_1") (pintype "passive"))
      (node (ref "R8") (pin "1") (pinfunction "1_1") (pintype "passive"))
      (node (ref "U1") (pin "9") (pinfunction "MCLR_9") (pintype "bidirectional"))
    )
    (net (code "16") (name "/MIC") (class "Default")
      (node (ref "R39") (pin "2") (pinfunction "2_2") (pintype "passive"))
      (node (ref "U1") (pin "19") (pinfunction "RH7/AN15_19") (pintype "bidirectional"))
      (node (ref "U6") (pin "1") (pinfunction "VOUT_1") (pintype "passive"))
    )
    (net (code "17") (name "/NTC") (class "Default")
      (node (ref "C8") (pin "2") (pinfunction "2_2") (pintype "passive"))
      (node (ref "R5") (pin "1") (pinfunction "1_1") (pintype "passive"))
      (node (ref "R7") (pin "2") (pinfunction "2_2") (pintype "passive"))
      (node (ref "U1") (pin "21") (pinfunction "RH5/AN13_21") (pintype "bidirectional"))
    )
    (net (code "18") (name "/OPTO_LED") (class "Default")
      (node (ref "R38") (pin "2") (pinfunction "2_2") (pintype "passive"))
      (node (ref "U1") (pin "69") (pinfunction "RD1/AD1_69") (pintype "bidirectional"))
    )
    (net (code "19") (name "/OPTO_TRT_DCH") (class "Default")
      (node (ref "C11") (pin "2") (pinfunction "2_2") (pintype "passive"))
      (node (ref "R27") (pin "1") (pinfunction "1_1") (pintype "passive"))
      (node (ref "U1") (pin "28") (pinfunction "RA2/AN2/VREF-_28") (pintype "input"))
    )
    (net (code "20") (name "/OPTO_TRT_IZQ") (class "Default")
      (node (ref "C13") (pin "2") (pinfunction "2_2") (pintype "passive"))
      (node (ref "R35") (pin "1") (pinfunction "1_1") (pintype "passive"))
      (node (ref "U1") (pin "33") (pinfunction "RA5/AN4_33") (pintype "bidirectional"))
    )
    (net (code "21") (name "/PIPELED_GREEN") (class "Default")
      (node (ref "J2") (pin "4") (pinfunction "4_4") (pintype "passive"))
      (node (ref "R9") (pin "1") (pinfunction "1_1") (pintype "passive"))
      (node (ref "U1") (pin "52") (pinfunction "RB6/KBI2/PGC_52") (pintype "bidirectional"))
    )
    (net (code "22") (name "/PIPELED_RED") (class "Default")
      (node (ref "R13") (pin "1") (pinfunction "1_1") (pintype "passive"))
      (node (ref "U1") (pin "53") (pinfunction "RB5/KBI1/PMA0_53") (pintype "bidirectional"))
    )
    (net (code "23") (name "/RF_CE") (class "Default")
      (node (ref "J4") (pin "3") (pinfunction "3_3") (pintype "passive"))
      (node (ref "R30") (pin "2") (pinfunction "2_2") (pintype "passive"))
    )
    (net (code "24") (name "/RF_CS") (class "Default")
      (node (ref "J4") (pin "4") (pinfunction "4_4") (pintype "passive"))
      (node (ref "R33") (pin "1") (pinfunction "1_1") (pintype "passive"))
    )
    (net (code "25") (name "/RF_IRQ") (class "Default")
      (node (ref "J4") (pin "8") (pinfunction "8_8") (pintype "passive"))
      (node (ref "R10") (pin "1") (pinfunction "1_1") (pintype "passive"))
    )
    (net (code "26") (name "/RF_SCK") (class "Default")
      (node (ref "J4") (pin "5") (pinfunction "5_5") (pintype "passive"))
      (node (ref "R16") (pin "1") (pinfunction "1_1") (pintype "passive"))
    )
    (net (code "27") (name "/RF_SDI") (class "Default")
      (node (ref "J4") (pin "7") (pinfunction "7_7") (pintype "passive"))
      (node (ref "R17") (pin "1") (pinfunction "1_1") (pintype "passive"))
    )
    (net (code "28") (name "/RF_SDO") (class "Default")
      (node (ref "J4") (pin "6") (pinfunction "6_6") (pintype "passive"))
      (node (ref "R18") (pin "1") (pinfunction "1_1") (pintype "passive"))
    )
    (net (code "29") (name "/SCL") (class "Default")
      (node (ref "R22") (pin "1") (pinfunction "1_1") (pintype "passive"))
      (node (ref "R28") (pin "1") (pinfunction "1_1") (pintype "passive"))
    )
    (net (code "30") (name "/SDA") (class "Default")
      (node (ref "R23") (pin "1") (pinfunction "1_1") (pintype "passive"))
      (node (ref "R29") (pin "1") (pinfunction "1_1") (pintype "passive"))
    )
    (net (code "31") (name "/SPEAKER") (class "Default")
      (node (ref "U1") (pin "55") (pinfunction "RB3/INT3/ECCP2_55") (pintype "bidirectional"))
      (node (ref "U5") (pin "1") (pinfunction "-_1") (pintype "power_in"))
    )
    (net (code "32") (name "/STAT_PROTECT") (class "Default")
      (node (ref "U1") (pin "72") (pinfunction "RD0/AD0_72") (pintype "bidirectional"))
    )
    (net (code "33") (name "/USB_CON_N") (class "Default")
      (node (ref "U8") (pin "2") (pinfunction "2_2") (pintype "passive"))
      (node (ref "U9") (pin "4") (pinfunction "I/O2_4") (pintype "passive"))
    )
    (net (code "34") (name "/USB_CON_P") (class "Default")
      (node (ref "U8") (pin "3") (pinfunction "3_3") (pintype "passive"))
      (node (ref "U9") (pin "6") (pinfunction "I/O1_6") (pintype "passive"))
    )
    (net (code "35") (name "/USB_N") (class "Default")
      (node (ref "U1") (pin "17") (pinfunction "RF3/D-_17") (pintype "bidirectional"))
      (node (ref "U9") (pin "3") (pinfunction "P-I/O2_3") (pintype "passive"))
    )
    (net (code "36") (name "/USB_P") (class "Default")
      (node (ref "U1") (pin "16") (pinfunction "RF4/D+_16") (pintype "bidirectional"))
      (node (ref "U9") (pin "1") (pinfunction "P-I/O1_1") (pintype "passive"))
    )
    (net (code "37") (name "/VBUS") (class "Default")
      (node (ref "F1") (pin "1") (pinfunction "1_1") (pintype "passive"))
      (node (ref "R36") (pin "1") (pinfunction "1_1") (pintype "passive"))
      (node (ref "R37") (pin "2") (pinfunction "2_2") (pintype "passive"))
    )
    (net (code "38") (name "GND") (class "Default")
      (node (ref "C1") (pin "1") (pinfunction "1_1") (pintype "passive"))
      (node (ref "C10") (pin "1") (pinfunction "1_1") (pintype "passive"))
      (node (ref "C11") (pin "1") (pinfunction "1_1") (pintype "passive"))
      (node (ref "C12") (pin "1") (pinfunction "1_1") (pintype "passive"))
      (node (ref "C13") (pin "1") (pinfunction "1_1") (pintype "passive"))
      (node (ref "C14") (pin "1") (pinfunction "1_1") (pintype "passive"))
      (node (ref "C15") (pin "1") (pinfunction "1_1") (pintype "passive"))
      (node (ref "C16") (pin "1") (pinfunction "1_1") (pintype "passive"))
      (node (ref "C17") (pin "1") (pinfunction "1_1") (pintype "passive"))
      (node (ref "C18") (pin "1") (pinfunction "1_1") (pintype "passive"))
      (node (ref "C2") (pin "1") (pinfunction "1_1") (pintype "passive"))
      (node (ref "C20") (pin "1") (pinfunction "1_1") (pintype "passive"))
      (node (ref "C3") (pin "1") (pinfunction "1_1") (pintype "passive"))
      (node (ref "C30") (pin "1") (pinfunction "1_1") (pintype "passive"))
      (node (ref "C4") (pin "1") (pinfunction "1_1") (pintype "passive"))
      (node (ref "C5") (pin "1") (pinfunction "1_1") (pintype "passive"))
      (node (ref "C6") (pin "1") (pinfunction "1_1") (pintype "passive"))
      (node (ref "C7") (pin "1") (pinfunction "1_1") (pintype "passive"))
      (node (ref "C8") (pin "1") (pinfunction "1_1") (pintype "passive"))
      (node (ref "C9") (pin "1") (pinfunction "1_1") (pintype "passive"))
      (node (ref "D11") (pin "1") (pinfunction "A_1") (pintype "passive"))
      (node (ref "J2") (pin "5") (pinfunction "5_5") (pintype "passive"))
      (node (ref "J3") (pin "6") (pinfunction "6_6") (pintype "passive"))
      (node (ref "J4") (pin "2") (pinfunction "2_2") (pintype "passive"))
      (node (ref "L2") (pin "1") (pinfunction "1_1") (pintype "passive"))
      (node (ref "MK1") (pin "1") (pinfunction "1_1") (pintype "passive"))
      (node (ref "Q1") (pin "2") (pinfunction "E_2") (pintype "passive"))
      (node (ref "Q2") (pin "2") (pinfunction "E_2") (pintype "passive"))
      (node (ref "Q3") (pin "2") (pinfunction "E_2") (pintype "passive"))
      (node (ref "Q4") (pin "2") (pinfunction "E_2") (pintype "passive"))
      (node (ref "R2") (pin "1") (pinfunction "1_1") (pintype "passive"))
      (node (ref "R37") (pin "1") (pinfunction "1_1") (pintype "passive"))
      (node (ref "R40") (pin "2") (pinfunction "2_2") (pintype "passive"))
      (node (ref "R41") (pin "1") (pinfunction "1_1") (pintype "passive"))
      (node (ref "R46") (pin "1") (pinfunction "1_1") (pintype "passive"))
      (node (ref "R7") (pin "1") (pinfunction "1_1") (pintype "passive"))
      (node (ref "U1") (pin "11") (pinfunction "VSS_11") (pintype "power_in"))
      (node (ref "U1") (pin "26") (pinfunction "AVSS_26") (pintype "power_in"))
      (node (ref "U1") (pin "31") (pinfunction "VSS_31") (pintype "power_in"))
      (node (ref "U1") (pin "51") (pinfunction "VSS_51") (pintype "power_in"))
      (node (ref "U1") (pin "70") (pinfunction "VSS_70") (pintype "power_in"))
      (node (ref "U2") (pin "3") (pinfunction "S'_3") (pintype "passive"))
      (node (ref "U3") (pin "3") (pinfunction "S'_3") (pintype "passive"))
      (node (ref "U5") (pin "2") (pinfunction "+_2") (pintype "power_in"))
      (node (ref "U6") (pin "5") (pinfunction "VSS_5") (pintype "passive"))
      (node (ref "U7") (pin "10") (pinfunction "GND_10") (pintype "passive"))
      (node (ref "U7") (pin "12") (pinfunction "GND_12") (pintype "passive"))
      (node (ref "U7") (pin "5") (pinfunction "GND_5") (pintype "passive"))
      (node (ref "U7") (pin "7") (pinfunction "SA0_7") (pintype "passive"))
      (node (ref "U9") (pin "2") (pinfunction "GND_2") (pintype "passive"))
    )
    (net (code "39") (name "Net-(C14-Pad2)") (class "Default")
      (node (ref "C14") (pin "2") (pinfunction "2_2") (pintype "passive"))
      (node (ref "F1") (pin "2") (pinfunction "2_2") (pintype "passive"))
      (node (ref "L1") (pin "1") (pinfunction "1_1") (pintype "passive"))
    )
    (net (code "40") (name "Net-(C19-Pad2)") (class "Default")
      (node (ref "C19") (pin "2") (pinfunction "2_2") (pintype "passive"))
      (node (ref "R44") (pin "2") (pinfunction "2_2") (pintype "passive"))
      (node (ref "U8") (pin "6") (pinfunction "6_6") (pintype "passive"))
      (node (ref "U8") (pin "7") (pinfunction "7_7") (pintype "passive"))
      (node (ref "U8") (pin "8") (pinfunction "8_8") (pintype "passive"))
      (node (ref "U8") (pin "9") (pinfunction "9_9") (pintype "passive"))
    )
    (net (code "41") (name "Net-(C21-Pad2)") (class "Default")
      (node (ref "C21") (pin "2") (pinfunction "2_2") (pintype "passive"))
      (node (ref "MK1") (pin "2") (pinfunction "2_2") (pintype "passive"))
      (node (ref "R45") (pin "1") (pinfunction "1_1") (pintype "passive"))
    )
    (net (code "42") (name "Net-(D1-A)") (class "Default")
      (node (ref "D1") (pin "2") (pinfunction "A_2") (pintype "passive"))
      (node (ref "D2") (pin "1") (pinfunction "K_1") (pintype "passive"))
    )
    (net (code "43") (name "Net-(D1-K)") (class "Default")
      (node (ref "D1") (pin "1") (pinfunction "K_1") (pintype "passive"))
      (node (ref "R1") (pin "2") (pinfunction "2_2") (pintype "passive"))
    )
    (net (code "44") (name "Net-(D3-K)") (class "Default")
      (node (ref "D3") (pin "1") (pinfunction "K_1") (pintype "passive"))
      (node (ref "R4") (pin "2") (pinfunction "2_2") (pintype "passive"))
    )
    (net (code "45") (name "Net-(D4-K)") (class "Default")
      (node (ref "D4") (pin "2") (pinfunction "K_2") (pintype "passive"))
      (node (ref "R9") (pin "2") (pinfunction "2_2") (pintype "passive"))
    )
    (net (code "46") (name "Net-(D5-K)") (class "Default")
      (node (ref "D5") (pin "2") (pinfunction "K_2") (pintype "passive"))
      (node (ref "R13") (pin "2") (pinfunction "2_2") (pintype "passive"))
    )
    (net (code "47") (name "Net-(D6-K)") (class "Default")
      (node (ref "D6") (pin "2") (pinfunction "K_2") (pintype "passive"))
      (node (ref "R14") (pin "2") (pinfunction "2_2") (pintype "passive"))
    )
    (net (code "48") (name "Net-(D7-K)") (class "Default")
      (node (ref "D7") (pin "1") (pinfunction "K_1") (pintype "passive"))
      (node (ref "R15") (pin "2") (pinfunction "2_2") (pintype "passive"))
    )
    (net (code "49") (name "Net-(D8-K)") (class "Default")
      (node (ref "D8") (pin "1") (pinfunction "K_1") (pintype "passive"))
      (node (ref "R20") (pin "2") (pinfunction "2_2") (pintype "passive"))
    )
    (net (code "50") (name "Net-(D11-10)") (class "Default")
      (node (ref "D11") (pin "2") (pinfunction "10_2") (pintype "passive"))
      (node (ref "L1") (pin "2") (pinfunction "2_2") (pintype "passive"))
      (node (ref "R40") (pin "1") (pinfunction "1_1") (pintype "passive"))
      (node (ref "U8") (pin "1") (pinfunction "1_1") (pintype "passive"))
    )
    (net (code "51") (name "Net-(L2-Pad2)") (class "Default")
      (node (ref "L2") (pin "2") (pinfunction "2_2") (pintype "passive"))
      (node (ref "U8") (pin "5") (pinfunction "5_5") (pintype "passive"))
    )
    (net (code "52") (name "Net-(Q1-B)") (class "Default")
      (node (ref "Q1") (pin "1") (pinfunction "B_1") (pintype "passive"))
      (node (ref "R3") (pin "2") (pinfunction "2_2") (pintype "passive"))
    )
    (net (code "53") (name "Net-(Q1-C)") (class "Default")
      (node (ref "Q1") (pin "3") (pinfunction "C_3") (pintype "passive"))
      (node (ref "R1") (pin "1") (pinfunction "1_1") (pintype "passive"))
    )
    (net (code "54") (name "Net-(Q2-B)") (class "Default")
      (node (ref "Q2") (pin "1") (pinfunction "B_1") (pintype "passive"))
      (node (ref "R6") (pin "2") (pinfunction "2_2") (pintype "passive"))
    )
    (net (code "55") (name "Net-(Q2-C)") (class "Default")
      (node (ref "Q2") (pin "3") (pinfunction "C_3") (pintype "passive"))
      (node (ref "R4") (pin "1") (pinfunction "1_1") (pintype "passive"))
    )
    (net (code "56") (name "Net-(Q3-B)") (class "Default")
      (node (ref "Q3") (pin "1") (pinfunction "B_1") (pintype "passive"))
      (node (ref "R21") (pin "2") (pinfunction "2_2") (pintype "passive"))
    )
    (net (code "57") (name "Net-(Q3-C)") (class "Default")
      (node (ref "Q3") (pin "3") (pinfunction "C_3") (pintype "passive"))
      (node (ref "R15") (pin "1") (pinfunction "1_1") (pintype "passive"))
      (node (ref "R20") (pin "1") (pinfunction "1_1") (pintype "passive"))
    )
    (net (code "58") (name "Net-(Q4-B)") (class "Default")
      (node (ref "Q4") (pin "1") (pinfunction "B_1") (pintype "passive"))
      (node (ref "R38") (pin "1") (pinfunction "1_1") (pintype "passive"))
    )
    (net (code "59") (name "Net-(Q4-C)") (class "Default")
      (node (ref "Q4") (pin "3") (pinfunction "C_3") (pintype "passive"))
      (node (ref "U2") (pin "1") (pinfunction "LEDA_1") (pintype "passive"))
      (node (ref "U3") (pin "1") (pinfunction "LEDA_1") (pintype "passive"))
    )
    (net (code "60") (name "Net-(U1-OSC1{slash}CLKI{slash}RA7)") (class "Default")
      (node (ref "C6") (pin "2") (pinfunction "2_2") (pintype "passive"))
      (node (ref "U1") (pin "49") (pinfunction "OSC1/CLKI/RA7_49") (pintype "input"))
      (node (ref "Y11") (pin "2") (pinfunction "OSC2_2") (pintype "passive"))
    )
    (net (code "61") (name "Net-(U1-OSC2{slash}CLKO{slash}RA6)") (class "Default")
      (node (ref "C7") (pin "2") (pinfunction "2_2") (pintype "passive"))
      (node (ref "U1") (pin "50") (pinfunction "OSC2/CLKO/RA6_50") (pintype "input"))
      (node (ref "Y11") (pin "1") (pinfunction "OSC1_1") (pintype "passive"))
    )
    (net (code "62") (name "Net-(U1-RA0{slash}AN0)") (class "Default")
      (node (ref "C5") (pin "2") (pinfunction "2_2") (pintype "passive"))
      (node (ref "J1") (pin "6") (pinfunction "6_6") (pintype "passive"))
      (node (ref "R2") (pin "2") (pinfunction "2_2") (pintype "passive"))
      (node (ref "U1") (pin "30") (pinfunction "RA0/AN0_30") (pintype "input"))
    )
    (net (code "63") (name "Net-(U1-RB0{slash}INT0)") (class "Default")
      (node (ref "R10") (pin "2") (pinfunction "2_2") (pintype "passive"))
      (node (ref "U1") (pin "58") (pinfunction "RB0/INT0_58") (pintype "bidirectional"))
    )
    (net (code "64") (name "Net-(U1-RB1{slash}INT1)") (class "Default")
      (node (ref "R11") (pin "2") (pinfunction "2_2") (pintype "passive"))
      (node (ref "U1") (pin "57") (pinfunction "RB1/INT1_57") (pintype "bidirectional"))
    )
    (net (code "65") (name "Net-(U1-RB2{slash}INT2)") (class "Default")
      (node (ref "R12") (pin "2") (pinfunction "2_2") (pintype "passive"))
      (node (ref "U1") (pin "56") (pinfunction "RB2/INT2_56") (pintype "bidirectional"))
    )
    (net (code "66") (name "Net-(U1-RB7{slash}KBI3{slash}PGD)") (class "Default")
      (node (ref "J2") (pin "3") (pinfunction "3_3") (pintype "passive"))
      (node (ref "U1") (pin "47") (pinfunction "RB7/KBI3/PGD_47") (pintype "bidirectional"))
    )
    (net (code "67") (name "Net-(U1-RC3{slash}SCK1{slash}SCL1)") (class "Default")
      (node (ref "R16") (pin "2") (pinfunction "2_2") (pintype "passive"))
      (node (ref "U1") (pin "44") (pinfunction "RC3/SCK1/SCL1_44") (pintype "bidirectional"))
    )
    (net (code "68") (name "Net-(U1-RC4{slash}SDI1{slash}SDA1)") (class "Default")
      (node (ref "R17") (pin "2") (pinfunction "2_2") (pintype "passive"))
      (node (ref "U1") (pin "45") (pinfunction "RC4/SDI1/SDA1_45") (pintype "bidirectional"))
    )
    (net (code "69") (name "Net-(U1-RC5{slash}SDO1)") (class "Default")
      (node (ref "R18") (pin "2") (pinfunction "2_2") (pintype "passive"))
      (node (ref "U1") (pin "46") (pinfunction "RC5/SDO1_46") (pintype "bidirectional"))
    )
    (net (code "70") (name "Net-(U1-RD5{slash}AD5{slash}SDA2)") (class "Default")
      (node (ref "R24") (pin "2") (pinfunction "2_2") (pintype "passive"))
      (node (ref "U1") (pin "65") (pinfunction "RD5/AD5/SDA2_65") (pintype "bidirectional"))
    )
    (net (code "71") (name "Net-(U1-RD6{slash}AD6{slash}SCK2{slash}SCL2)") (class "Default")
      (node (ref "R25") (pin "2") (pinfunction "2_2") (pintype "passive"))
      (node (ref "U1") (pin "64") (pinfunction "RD6/AD6/SCK2/SCL2_64") (pintype "bidirectional"))
    )
    (net (code "72") (name "Net-(U1-RE0{slash}AD8)") (class "Default")
      (node (ref "R28") (pin "2") (pinfunction "2_2") (pintype "passive"))
      (node (ref "U1") (pin "4") (pinfunction "RE0/AD8_4") (pintype "bidirectional"))
    )
    (net (code "73") (name "Net-(U1-RE1{slash}AD9)") (class "Default")
      (node (ref "R29") (pin "2") (pinfunction "2_2") (pintype "passive"))
      (node (ref "U1") (pin "3") (pinfunction "RE1/AD9_3") (pintype "bidirectional"))
    )
    (net (code "74") (name "Net-(U1-RE7{slash}AD15)") (class "Default")
      (node (ref "R32") (pin "2") (pinfunction "2_2") (pintype "passive"))
      (node (ref "U1") (pin "73") (pinfunction "RE7/AD15_73") (pintype "bidirectional"))
    )
    (net (code "75") (name "Net-(U1-RF2{slash}AN7)") (class "Default")
      (node (ref "R33") (pin "2") (pinfunction "2_2") (pintype "passive"))
      (node (ref "U1") (pin "18") (pinfunction "RF2/AN7_18") (pintype "bidirectional"))
    )
    (net (code "76") (name "Net-(U1-RF7{slash}SS)") (class "Default")
      (node (ref "R36") (pin "2") (pinfunction "2_2") (pintype "passive"))
      (node (ref "U1") (pin "13") (pinfunction "RF7/SS_13") (pintype "bidirectional"))
    )
    (net (code "77") (name "Net-(U1-RH4{slash}AN12)") (class "Default")
      (node (ref "R30") (pin "1") (pinfunction "1_1") (pintype "passive"))
      (node (ref "U1") (pin "22") (pinfunction "RH4/AN12_22") (pintype "bidirectional"))
    )
    (net (code "78") (name "Net-(U1-VDDCORE{slash}VCAP)") (class "Default")
      (node (ref "C10") (pin "2") (pinfunction "2_2") (pintype "passive"))
      (node (ref "C9") (pin "2") (pinfunction "2_2") (pintype "passive"))
      (node (ref "U1") (pin "12") (pinfunction "VDDCORE/VCAP_12") (pintype "power_in"))
    )
    (net (code "79") (name "Net-(U2-2)") (class "Default")
      (node (ref "R26") (pin "1") (pinfunction "1_1") (pintype "passive"))
      (node (ref "R27") (pin "2") (pinfunction "2_2") (pintype "passive"))
      (node (ref "U2") (pin "4") (pinfunction "2_4") (pintype "power_in"))
    )
    (net (code "80") (name "Net-(U2-4)") (class "Default")
      (node (ref "R19") (pin "2") (pinfunction "2_2") (pintype "passive"))
      (node (ref "U2") (pin "2") (pinfunction "4_2") (pintype "power_in"))
    )
    (net (code "81") (name "Net-(U3-2)") (class "Default")
      (node (ref "R34") (pin "1") (pinfunction "1_1") (pintype "passive"))
      (node (ref "R35") (pin "2") (pinfunction "2_2") (pintype "passive"))
      (node (ref "U3") (pin "4") (pinfunction "2_4") (pintype "power_in"))
    )
    (net (code "82") (name "Net-(U3-4)") (class "Default")
      (node (ref "R31") (pin "2") (pinfunction "2_2") (pintype "passive"))
      (node (ref "U3") (pin "2") (pinfunction "4_2") (pintype "power_in"))
    )
    (net (code "83") (name "Net-(U6-VIN+)") (class "Default")
      (node (ref "C21") (pin "1") (pinfunction "1_1") (pintype "passive"))
      (node (ref "R46") (pin "2") (pinfunction "2_2") (pintype "passive"))
      (node (ref "U6") (pin "3") (pinfunction "VIN+_3") (pintype "passive"))
    )
    (net (code "84") (name "Net-(U6-VIN-)") (class "Default")
      (node (ref "R39") (pin "1") (pinfunction "1_1") (pintype "passive"))
      (node (ref "R41") (pin "2") (pinfunction "2_2") (pintype "passive"))
      (node (ref "U6") (pin "4") (pinfunction "VIN-_4") (pintype "passive"))
    )
    (net (code "85") (name "Net-(U7-BYP)") (class "Default")
      (node (ref "C17") (pin "2") (pinfunction "2_2") (pintype "passive"))
      (node (ref "U7") (pin "2") (pinfunction "BYP_2") (pintype "passive"))
    )
    (net (code "86") (name "VCC") (class "Default")
      (node (ref "C1") (pin "2") (pinfunction "2_2") (pintype "passive"))
      (node (ref "C12") (pin "2") (pinfunction "2_2") (pintype "passive"))
      (node (ref "C15") (pin "2") (pinfunction "2_2") (pintype "passive"))
      (node (ref "C16") (pin "2") (pinfunction "2_2") (pintype "passive"))
      (node (ref "C18") (pin "2") (pinfunction "2_2") (pintype "passive"))
      (node (ref "C2") (pin "2") (pinfunction "2_2") (pintype "passive"))
      (node (ref "C20") (pin "2") (pinfunction "2_2") (pintype "passive"))
      (node (ref "C3") (pin "2") (pinfunction "2_2") (pintype "passive"))
      (node (ref "C4") (pin "2") (pinfunction "2_2") (pintype "passive"))
      (node (ref "D2") (pin "2") (pinfunction "A_2") (pintype "passive"))
      (node (ref "D3") (pin "2") (pinfunction "A_2") (pintype "passive"))
      (node (ref "D4") (pin "1") (pinfunction "A_1") (pintype "passive"))
      (node (ref "D5") (pin "1") (pinfunction "A_1") (pintype "passive"))
      (node (ref "D6") (pin "1") (pinfunction "A_1") (pintype "passive"))
      (node (ref "D7") (pin "2") (pinfunction "A_2") (pintype "passive"))
      (node (ref "D8") (pin "2") (pinfunction "A_2") (pintype "passive"))
      (node (ref "J1") (pin "1") (pinfunction "1_1") (pintype "passive"))
      (node (ref "J2") (pin "1") (pinfunction "1_1") (pintype "passive"))
      (node (ref "J3") (pin "1") (pinfunction "1_1") (pintype "passive"))
      (node (ref "J4") (pin "1") (pinfunction "1_1") (pintype "passive"))
      (node (ref "R19") (pin "1") (pinfunction "1_1") (pintype "passive"))
      (node (ref "R22") (pin "2") (pinfunction "2_2") (pintype "passive"))
      (node (ref "R23") (pin "2") (pinfunction "2_2") (pintype "passive"))
      (node (ref "R26") (pin "2") (pinfunction "2_2") (pintype "passive"))
      (node (ref "R31") (pin "1") (pinfunction "1_1") (pintype "passive"))
      (node (ref "R34") (pin "2") (pinfunction "2_2") (pintype "passive"))
      (node (ref "R42") (pin "2") (pinfunction "2_2") (pintype "passive"))
      (node (ref "R43") (pin "2") (pinfunction "2_2") (pintype "passive"))
      (node (ref "R45") (pin "2") (pinfunction "2_2") (pintype "passive"))
      (node (ref "R5") (pin "2") (pinfunction "2_2") (pintype "passive"))
      (node (ref "R8") (pin "2") (pinfunction "2_2") (pintype "passive"))
      (node (ref "U1") (pin "23") (pinfunction "VUSB_23") (pintype "bidirectional"))
      (node (ref "U1") (pin "24") (pinfunction "ENVREG_24") (pintype "bidirectional"))
      (node (ref "U1") (pin "25") (pinfunction "AVDD_25") (pintype "power_in"))
      (node (ref "U1") (pin "32") (pinfunction "VDD_32") (pintype "power_in"))
      (node (ref "U1") (pin "48") (pinfunction "VDD_48") (pintype "power_in"))
      (node (ref "U1") (pin "71") (pinfunction "VDD_71") (pintype "power_in"))
      (node (ref "U6") (pin "2") (pinfunction "VDD_2") (pintype "passive"))
      (node (ref "U7") (pin "1") (pinfunction "VDDIO_1") (pintype "passive"))
      (node (ref "U7") (pin "14") (pinfunction "VDD_14") (pintype "passive"))
    )
    (net (code "87") (name "unconnected-(J1-Pad2)") (class "Default")
      (node (ref "J1") (pin "2") (pinfunction "2_2") (pintype "passive+no_connect"))
    )
    (net (code "88") (name "unconnected-(J1-Pad3)") (class "Default")
      (node (ref "J1") (pin "3") (pinfunction "3_3") (pintype "passive+no_connect"))
    )
    (net (code "89") (name "unconnected-(J1-Pad4)") (class "Default")
      (node (ref "J1") (pin "4") (pinfunction "4_4") (pintype "passive+no_connect"))
    )
    (net (code "90") (name "unconnected-(J1-Pad5)") (class "Default")
      (node (ref "J1") (pin "5") (pinfunction "5_5") (pintype "passive+no_connect"))
    )
    (net (code "91") (name "unconnected-(U1-RA4{slash}T0CKI-Pad34)") (class "Default")
      (node (ref "U1") (pin "34") (pinfunction "RA4/T0CKI_34") (pintype "bidirectional+no_connect"))
    )
    (net (code "92") (name "unconnected-(U1-RB4{slash}KBI0{slash}PMA1-Pad54)") (class "Default")
      (node (ref "U1") (pin "54") (pinfunction "RB4/KBI0/PMA1_54") (pintype "bidirectional+no_connect"))
    )
    (net (code "93") (name "unconnected-(U1-RC0{slash}T1OSO{slash}T13CKI-Pad36)") (class "Default")
      (node (ref "U1") (pin "36") (pinfunction "RC0/T1OSO/T13CKI_36") (pintype "bidirectional+no_connect"))
    )
    (net (code "94") (name "unconnected-(U1-RC1{slash}T1OSI{slash}ECCP2-Pad35)") (class "Default")
      (node (ref "U1") (pin "35") (pinfunction "RC1/T1OSI/ECCP2_35") (pintype "bidirectional+no_connect"))
    )
    (net (code "95") (name "unconnected-(U1-RC2{slash}CCP1-Pad43)") (class "Default")
      (node (ref "U1") (pin "43") (pinfunction "RC2/CCP1_43") (pintype "bidirectional+no_connect"))
    )
    (net (code "96") (name "unconnected-(U1-RC6{slash}TX1{slash}CK1-Pad37)") (class "Default")
      (node (ref "U1") (pin "37") (pinfunction "RC6/TX1/CK1_37") (pintype "bidirectional+no_connect"))
    )
    (net (code "97") (name "unconnected-(U1-RD2{slash}AD2-Pad68)") (class "Default")
      (node (ref "U1") (pin "68") (pinfunction "RD2/AD2_68") (pintype "bidirectional+no_connect"))
    )
    (net (code "98") (name "unconnected-(U1-RD3{slash}AD3-Pad67)") (class "Default")
      (node (ref "U1") (pin "67") (pinfunction "RD3/AD3_67") (pintype "bidirectional+no_connect"))
    )
    (net (code "99") (name "unconnected-(U1-RD4{slash}AD4{slash}SDO2-Pad66)") (class "Default")
      (node (ref "U1") (pin "66") (pinfunction "RD4/AD4/SDO2_66") (pintype "bidirectional+no_connect"))
    )
    (net (code "100") (name "unconnected-(U1-RD7{slash}AD7{slash}SS2-Pad63)") (class "Default")
      (node (ref "U1") (pin "63") (pinfunction "RD7/AD7/SS2_63") (pintype "bidirectional+no_connect"))
    )
    (net (code "101") (name "unconnected-(U1-RE2{slash}AD10-Pad78)") (class "Default")
      (node (ref "U1") (pin "78") (pinfunction "RE2/AD10_78") (pintype "bidirectional+no_connect"))
    )
    (net (code "102") (name "unconnected-(U1-RE3{slash}AD11-Pad77)") (class "Default")
      (node (ref "U1") (pin "77") (pinfunction "RE3/AD11_77") (pintype "bidirectional+no_connect"))
    )
    (net (code "103") (name "unconnected-(U1-RE4{slash}AD12-Pad76)") (class "Default")
      (node (ref "U1") (pin "76") (pinfunction "RE4/AD12_76") (pintype "bidirectional+no_connect"))
    )
    (net (code "104") (name "unconnected-(U1-RE6{slash}AD14-Pad74)") (class "Default")
      (node (ref "U1") (pin "74") (pinfunction "RE6/AD14_74") (pintype "bidirectional+no_connect"))
    )
    (net (code "105") (name "unconnected-(U1-RG0{slash}PMA8{slash}ECCP3-Pad5)") (class "Default")
      (node (ref "U1") (pin "5") (pinfunction "RG0/PMA8/ECCP3_5") (pintype "bidirectional+no_connect"))
    )
    (net (code "106") (name "unconnected-(U1-RG1{slash}TX2{slash}CK2-Pad6)") (class "Default")
      (node (ref "U1") (pin "6") (pinfunction "RG1/TX2/CK2_6") (pintype "bidirectional+no_connect"))
    )
    (net (code "107") (name "unconnected-(U1-RG2{slash}RX2{slash}DT2-Pad7)") (class "Default")
      (node (ref "U1") (pin "7") (pinfunction "RG2/RX2/DT2_7") (pintype "bidirectional+no_connect"))
    )
    (net (code "108") (name "unconnected-(U1-RG3{slash}CCP4-Pad8)") (class "Default")
      (node (ref "U1") (pin "8") (pinfunction "RG3/CCP4_8") (pintype "bidirectional+no_connect"))
    )
    (net (code "109") (name "unconnected-(U1-RG4{slash}CCP5-Pad10)") (class "Default")
      (node (ref "U1") (pin "10") (pinfunction "RG4/CCP5_10") (pintype "bidirectional+no_connect"))
    )
    (net (code "110") (name "unconnected-(U1-RH0{slash}A16-Pad79)") (class "Default")
      (node (ref "U1") (pin "79") (pinfunction "RH0/A16_79") (pintype "bidirectional+no_connect"))
    )
    (net (code "111") (name "unconnected-(U1-RH1{slash}A17-Pad80)") (class "Default")
      (node (ref "U1") (pin "80") (pinfunction "RH1/A17_80") (pintype "bidirectional+no_connect"))
    )
    (net (code "112") (name "unconnected-(U1-RH2{slash}A18-Pad1)") (class "Default")
      (node (ref "U1") (pin "1") (pinfunction "RH2/A18_1") (pintype "bidirectional+no_connect"))
    )
    (net (code "113") (name "unconnected-(U1-RH3{slash}A19-Pad2)") (class "Default")
      (node (ref "U1") (pin "2") (pinfunction "RH3/A19_2") (pintype "bidirectional+no_connect"))
    )
    (net (code "114") (name "unconnected-(U1-RJ0{slash}ALE-Pad62)") (class "Default")
      (node (ref "U1") (pin "62") (pinfunction "RJ0/ALE_62") (pintype "bidirectional+no_connect"))
    )
    (net (code "115") (name "unconnected-(U1-RJ1{slash}OE-Pad61)") (class "Default")
      (node (ref "U1") (pin "61") (pinfunction "RJ1/OE_61") (pintype "bidirectional+no_connect"))
    )
    (net (code "116") (name "unconnected-(U1-RJ2{slash}WRL-Pad60)") (class "Default")
      (node (ref "U1") (pin "60") (pinfunction "RJ2/WRL_60") (pintype "bidirectional+no_connect"))
    )
    (net (code "117") (name "unconnected-(U1-RJ3{slash}WRH-Pad59)") (class "Default")
      (node (ref "U1") (pin "59") (pinfunction "RJ3/WRH_59") (pintype "bidirectional+no_connect"))
    )
    (net (code "118") (name "unconnected-(U1-RJ4{slash}BAO-Pad39)") (class "Default")
      (node (ref "U1") (pin "39") (pinfunction "RJ4/BAO_39") (pintype "bidirectional+no_connect"))
    )
    (net (code "119") (name "unconnected-(U1-RJ5{slash}CE-Pad40)") (class "Default")
      (node (ref "U1") (pin "40") (pinfunction "RJ5/CE_40") (pintype "bidirectional+no_connect"))
    )
    (net (code "120") (name "unconnected-(U7-DNC-Pad3)") (class "Default")
      (node (ref "U7") (pin "3") (pinfunction "DNC_3") (pintype "passive+no_connect"))
    )
    (net (code "121") (name "unconnected-(U7-NC-Pad8)") (class "Default")
      (node (ref "U7") (pin "8") (pinfunction "NC_8") (pintype "passive+no_connect"))
    )
    (net (code "122") (name "unconnected-(U7-NC-Pad13)") (class "Default")
      (node (ref "U7") (pin "13") (pinfunction "NC_13") (pintype "passive+no_connect"))
    )
    (net (code "123") (name "unconnected-(U7-NC-Pad15)") (class "Default")
      (node (ref "U7") (pin "15") (pinfunction "NC_15") (pintype "passive+no_connect"))
    )
    (net (code "124") (name "unconnected-(U7-NC-Pad16)") (class "Default")
      (node (ref "U7") (pin "16") (pinfunction "NC_16") (pintype "passive+no_connect"))
    )
    (net (code "125") (name "unconnected-(U8-Pad4)") (class "Default")
      (node (ref "U8") (pin "4") (pinfunction "4_4") (pintype "passive+no_connect"))
    )
    (net (code "126") (name "unconnected-(U9-NC-Pad5)") (class "Default")
      (node (ref "U9") (pin "5") (pinfunction "NC_5") (pintype "passive+no_connect"))
    )
  )
)
